# IRAMX-drv-v1.net
KiCad netlist of a schematic drawn in EAGLE
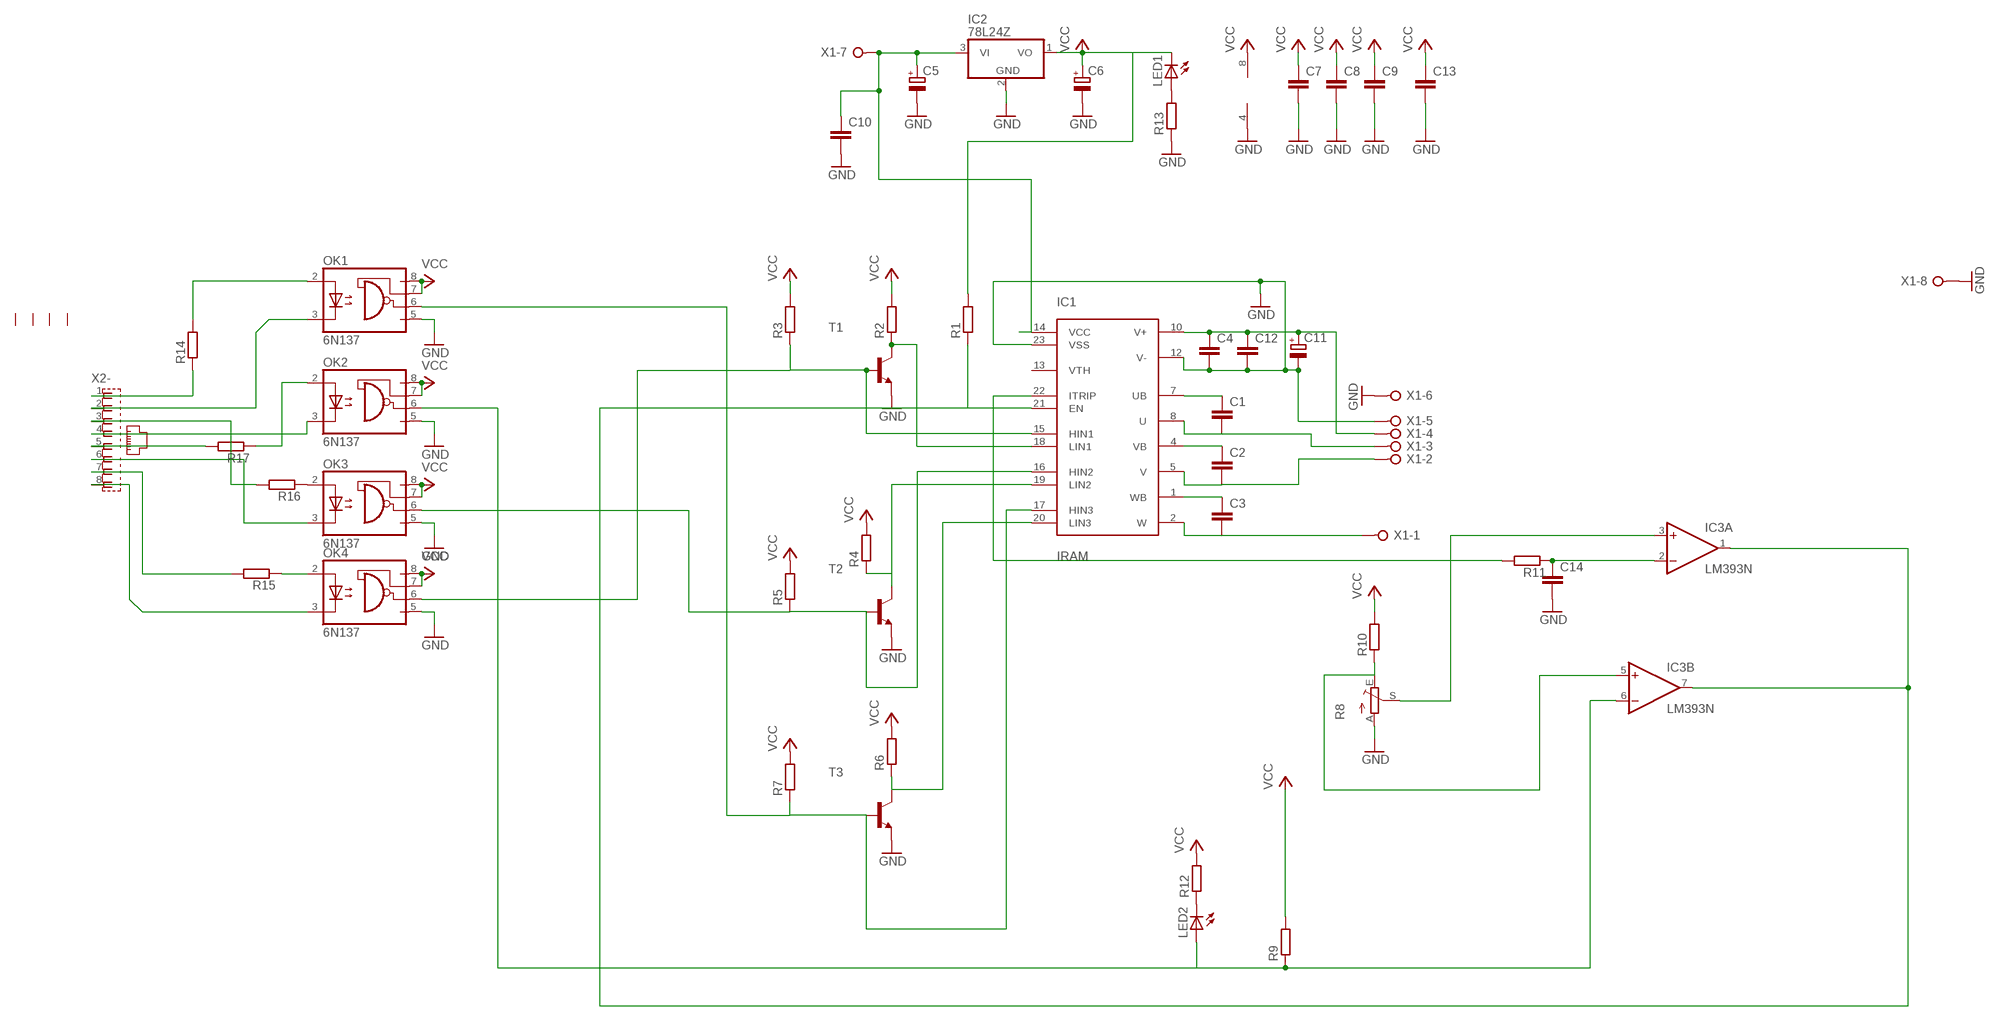
[diagram p0: schematic, sheet 1]

(export (version "E")
  (design (tool "Eeschema 10.0.6"))
  (components
    (comp (ref "C1")
      (value "C5/5")
      (footprint "eagle-import:C5B5")
      (libsource (lib "eagle-import") (part "C5/5"))
    )
    (comp (ref "C2")
      (value "C5/5")
      (footprint "eagle-import:C5B5")
      (libsource (lib "eagle-import") (part "C5/5"))
    )
    (comp (ref "C3")
      (value "C5/5")
      (footprint "eagle-import:C5B5")
      (libsource (lib "eagle-import") (part "C5/5"))
    )
    (comp (ref "C4")
      (value "C5/5")
      (footprint "eagle-import:C5B5")
      (libsource (lib "eagle-import") (part "C5/5"))
    )
    (comp (ref "C5")
      (value "CPOL-EUE2.5-5")
      (footprint "eagle-import:E2,5-5")
      (libsource (lib "eagle-import") (part "CPOL-EUE2.5-5"))
    )
    (comp (ref "C6")
      (value "CPOL-EUE2.5-5")
      (footprint "eagle-import:E2,5-5")
      (libsource (lib "eagle-import") (part "CPOL-EUE2.5-5"))
    )
    (comp (ref "C7")
      (value "C-EU050-025X075")
      (footprint "eagle-import:C050-025X075")
      (libsource (lib "eagle-import") (part "C-EU050-025X075"))
    )
    (comp (ref "C8")
      (value "C-EU050-025X075")
      (footprint "eagle-import:C050-025X075")
      (libsource (lib "eagle-import") (part "C-EU050-025X075"))
    )
    (comp (ref "C9")
      (value "C-EU050-025X075")
      (footprint "eagle-import:C050-025X075")
      (libsource (lib "eagle-import") (part "C-EU050-025X075"))
    )
    (comp (ref "C10")
      (value "C-EU050-025X075")
      (footprint "eagle-import:C050-025X075")
      (libsource (lib "eagle-import") (part "C-EU050-025X075"))
    )
    (comp (ref "C11")
      (value "CPOL-EUE10-25")
      (footprint "eagle-import:EB25D")
      (libsource (lib "eagle-import") (part "CPOL-EUE10-25"))
    )
    (comp (ref "C12")
      (value "C-EU150-054X183")
      (footprint "eagle-import:C150-054X183")
      (libsource (lib "eagle-import") (part "C-EU150-054X183"))
    )
    (comp (ref "C13")
      (value "C-EU050-025X075")
      (footprint "eagle-import:C050-025X075")
      (libsource (lib "eagle-import") (part "C-EU050-025X075"))
    )
    (comp (ref "C14")
      (value "C-EU050-025X075")
      (footprint "eagle-import:C050-025X075")
      (libsource (lib "eagle-import") (part "C-EU050-025X075"))
    )
    (comp (ref "IC1")
      (value "IRAM")
      (footprint "eagle-import:SIP23")
      (libsource (lib "eagle-import") (part "IRAM"))
    )
    (comp (ref "IC2")
      (value "78L24Z")
      (footprint "eagle-import:TO92")
      (libsource (lib "eagle-import") (part "78ZL24"))
    )
    (comp (ref "IC3")
      (value "LM393N")
      (footprint "eagle-import:DIL08")
      (libsource (lib "eagle-import") (part "LM393N"))
    )
    (comp (ref "LED1")
      (value "LED5MM")
      (footprint "eagle-import:LED5MM")
      (libsource (lib "eagle-import") (part "LED5MM"))
    )
    (comp (ref "LED2")
      (value "LED5MM")
      (footprint "eagle-import:LED5MM")
      (libsource (lib "eagle-import") (part "LED5MM"))
    )
    (comp (ref "OK1")
      (value "6N137")
      (footprint "eagle-import:DIL08")
      (libsource (lib "eagle-import") (part "6N137"))
    )
    (comp (ref "OK2")
      (value "6N137")
      (footprint "eagle-import:DIL08")
      (libsource (lib "eagle-import") (part "6N137"))
    )
    (comp (ref "OK3")
      (value "6N137")
      (footprint "eagle-import:DIL08")
      (libsource (lib "eagle-import") (part "6N137"))
    )
    (comp (ref "OK4")
      (value "6N137")
      (footprint "eagle-import:DIL08")
      (libsource (lib "eagle-import") (part "6N137"))
    )
    (comp (ref "R1")
      (value "R-EU_0204/7")
      (footprint "eagle-import:0204_7")
      (libsource (lib "eagle-import") (part "R-EU_0204/7"))
    )
    (comp (ref "R2")
      (value "R-EU_0204/7")
      (footprint "eagle-import:0204_7")
      (libsource (lib "eagle-import") (part "R-EU_0204/7"))
    )
    (comp (ref "R3")
      (value "R-EU_0204/7")
      (footprint "eagle-import:0204_7")
      (libsource (lib "eagle-import") (part "R-EU_0204/7"))
    )
    (comp (ref "R4")
      (value "R-EU_0204/7")
      (footprint "eagle-import:0204_7")
      (libsource (lib "eagle-import") (part "R-EU_0204/7"))
    )
    (comp (ref "R5")
      (value "R-EU_0204/7")
      (footprint "eagle-import:0204_7")
      (libsource (lib "eagle-import") (part "R-EU_0204/7"))
    )
    (comp (ref "R6")
      (value "R-EU_0204/7")
      (footprint "eagle-import:0204_7")
      (libsource (lib "eagle-import") (part "R-EU_0204/7"))
    )
    (comp (ref "R7")
      (value "R-EU_0204/7")
      (footprint "eagle-import:0204_7")
      (libsource (lib "eagle-import") (part "R-EU_0204/7"))
    )
    (comp (ref "R8")
      (value "TRIM_EU-CA6V")
      (footprint "eagle-import:CA6V")
      (libsource (lib "eagle-import") (part "TRIM_EU-CA6V"))
    )
    (comp (ref "R9")
      (value "R-EU_0204/7")
      (footprint "eagle-import:0204_7")
      (libsource (lib "eagle-import") (part "R-EU_0204/7"))
    )
    (comp (ref "R10")
      (value "R-EU_0204/7")
      (footprint "eagle-import:0204_7")
      (libsource (lib "eagle-import") (part "R-EU_0204/7"))
    )
    (comp (ref "R11")
      (value "R-EU_0204/7")
      (footprint "eagle-import:0204_7")
      (libsource (lib "eagle-import") (part "R-EU_0204/7"))
    )
    (comp (ref "R12")
      (value "R-EU_0204/7")
      (footprint "eagle-import:0204_7")
      (libsource (lib "eagle-import") (part "R-EU_0204/7"))
    )
    (comp (ref "R13")
      (value "R-EU_0204/7")
      (footprint "eagle-import:0204_7")
      (libsource (lib "eagle-import") (part "R-EU_0204/7"))
    )
    (comp (ref "R14")
      (value "R-EU_0204/2V")
      (footprint "eagle-import:0204V")
      (libsource (lib "eagle-import") (part "R-EU_0204/2V"))
    )
    (comp (ref "R15")
      (value "R-EU_0204/2V")
      (footprint "eagle-import:0204V")
      (libsource (lib "eagle-import") (part "R-EU_0204/2V"))
    )
    (comp (ref "R16")
      (value "R-EU_0204/2V")
      (footprint "eagle-import:0204V")
      (libsource (lib "eagle-import") (part "R-EU_0204/2V"))
    )
    (comp (ref "R17")
      (value "R-EU_0204/2V")
      (footprint "eagle-import:0204V")
      (libsource (lib "eagle-import") (part "R-EU_0204/2V"))
    )
    (comp (ref "T1")
      (value "BC547-NPN-TO92-CBE")
      (footprint "eagle-import:TO92-CBE")
      (libsource (lib "eagle-import") (part "-NPN-TO92-CBEBC547"))
    )
    (comp (ref "T2")
      (value "BC547-NPN-TO92-CBE")
      (footprint "eagle-import:TO92-CBE")
      (libsource (lib "eagle-import") (part "-NPN-TO92-CBEBC547"))
    )
    (comp (ref "T3")
      (value "BC547-NPN-TO92-CBE")
      (footprint "eagle-import:TO92-CBE")
      (libsource (lib "eagle-import") (part "-NPN-TO92-CBEBC547"))
    )
    (comp (ref "X1")
      (value "W237-08P")
      (footprint "eagle-import:W237-8P")
      (libsource (lib "eagle-import") (part "W237-08P"))
    )
    (comp (ref "X2")
      (value "RJ45")
      (footprint "eagle-import:RJ45")
      (libsource (lib "eagle-import") (part "RJ45"))
    )
  )
  (nets
    (net (code "1") (name "GND") (class "Default")
      (node (ref "C10") (pin "2") (pinfunction "2_2") (pintype "passive"))
      (node (ref "C11") (pin "-") (pinfunction "-_-") (pintype "passive"))
      (node (ref "C12") (pin "2") (pinfunction "2_2") (pintype "passive"))
      (node (ref "C13") (pin "2") (pinfunction "2_2") (pintype "passive"))
      (node (ref "C14") (pin "2") (pinfunction "2_2") (pintype "passive"))
      (node (ref "C4") (pin "2") (pinfunction "2_2") (pintype "passive"))
      (node (ref "C5") (pin "-") (pinfunction "-_-") (pintype "passive"))
      (node (ref "C6") (pin "-") (pinfunction "-_-") (pintype "passive"))
      (node (ref "C7") (pin "2") (pinfunction "2_2") (pintype "passive"))
      (node (ref "C8") (pin "2") (pinfunction "2_2") (pintype "passive"))
      (node (ref "C9") (pin "2") (pinfunction "2_2") (pintype "passive"))
      (node (ref "IC1") (pin "12") (pinfunction "V-_12") (pintype "bidirectional"))
      (node (ref "IC1") (pin "23") (pinfunction "VSS_23") (pintype "bidirectional"))
      (node (ref "IC2") (pin "2") (pinfunction "GND_2") (pintype "passive"))
      (node (ref "IC3") (pin "4") (pinfunction "V-_4") (pintype "power_in"))
      (node (ref "OK1") (pin "5") (pinfunction "GND_5") (pintype "passive"))
      (node (ref "OK2") (pin "5") (pinfunction "GND_5") (pintype "passive"))
      (node (ref "OK3") (pin "5") (pinfunction "GND_5") (pintype "passive"))
      (node (ref "OK4") (pin "5") (pinfunction "GND_5") (pintype "passive"))
      (node (ref "R13") (pin "1") (pinfunction "1_1") (pintype "passive"))
      (node (ref "R8") (pin "A") (pinfunction "A_A") (pintype "passive"))
      (node (ref "T1") (pin "E") (pinfunction "E_E") (pintype "passive"))
      (node (ref "T2") (pin "E") (pinfunction "E_E") (pintype "passive"))
      (node (ref "T3") (pin "E") (pinfunction "E_E") (pintype "passive"))
      (node (ref "X1") (pin "5") (pinfunction "KL_5") (pintype "passive"))
      (node (ref "X1") (pin "6") (pinfunction "KL_6") (pintype "passive"))
      (node (ref "X1") (pin "8") (pinfunction "KL_8") (pintype "passive"))
    )
    (net (code "2") (name "Net-(IC1-EN)") (class "Default")
      (node (ref "IC1") (pin "21") (pinfunction "EN_21") (pintype "bidirectional"))
      (node (ref "IC3") (pin "1") (pinfunction "OUT_1") (pintype "output"))
      (node (ref "IC3") (pin "7") (pinfunction "OUT_7") (pintype "output"))
      (node (ref "R1") (pin "1") (pinfunction "1_1") (pintype "passive"))
    )
    (net (code "3") (name "Net-(IC1-HIN1)") (class "Default")
      (node (ref "IC1") (pin "15") (pinfunction "HIN1_15") (pintype "bidirectional"))
      (node (ref "OK4") (pin "6") (pinfunction "VO_6") (pintype "passive"))
      (node (ref "R3") (pin "1") (pinfunction "1_1") (pintype "passive"))
      (node (ref "T1") (pin "B") (pinfunction "B_B") (pintype "passive"))
    )
    (net (code "4") (name "Net-(IC1-HIN2)") (class "Default")
      (node (ref "IC1") (pin "16") (pinfunction "HIN2_16") (pintype "bidirectional"))
      (node (ref "OK3") (pin "6") (pinfunction "VO_6") (pintype "passive"))
      (node (ref "R5") (pin "1") (pinfunction "1_1") (pintype "passive"))
      (node (ref "T2") (pin "B") (pinfunction "B_B") (pintype "passive"))
    )
    (net (code "5") (name "Net-(IC1-HIN3)") (class "Default")
      (node (ref "IC1") (pin "17") (pinfunction "HIN3_17") (pintype "bidirectional"))
      (node (ref "OK1") (pin "6") (pinfunction "VO_6") (pintype "passive"))
      (node (ref "R7") (pin "1") (pinfunction "1_1") (pintype "passive"))
      (node (ref "T3") (pin "B") (pinfunction "B_B") (pintype "passive"))
    )
    (net (code "6") (name "Net-(IC1-ITRIP)") (class "Default")
      (node (ref "IC1") (pin "22") (pinfunction "ITRIP_22") (pintype "bidirectional"))
      (node (ref "R11") (pin "2") (pinfunction "2_2") (pintype "passive"))
    )
    (net (code "7") (name "Net-(IC1-LIN1)") (class "Default")
      (node (ref "IC1") (pin "18") (pinfunction "LIN1_18") (pintype "bidirectional"))
      (node (ref "R2") (pin "1") (pinfunction "1_1") (pintype "passive"))
      (node (ref "T1") (pin "C") (pinfunction "C_C") (pintype "passive"))
    )
    (net (code "8") (name "Net-(IC1-LIN2)") (class "Default")
      (node (ref "IC1") (pin "19") (pinfunction "LIN2_19") (pintype "bidirectional"))
      (node (ref "R4") (pin "1") (pinfunction "1_1") (pintype "passive"))
      (node (ref "T2") (pin "C") (pinfunction "C_C") (pintype "passive"))
    )
    (net (code "9") (name "Net-(IC1-LIN3)") (class "Default")
      (node (ref "IC1") (pin "20") (pinfunction "LIN3_20") (pintype "bidirectional"))
      (node (ref "R6") (pin "1") (pinfunction "1_1") (pintype "passive"))
      (node (ref "T3") (pin "C") (pinfunction "C_C") (pintype "passive"))
    )
    (net (code "10") (name "Net-(IC1-U)") (class "Default")
      (node (ref "C1") (pin "2") (pinfunction "2_2") (pintype "passive"))
      (node (ref "IC1") (pin "8") (pinfunction "U_8") (pintype "bidirectional"))
      (node (ref "X1") (pin "3") (pinfunction "KL_3") (pintype "passive"))
    )
    (net (code "11") (name "Net-(IC1-UB)") (class "Default")
      (node (ref "C1") (pin "1") (pinfunction "1_1") (pintype "passive"))
      (node (ref "IC1") (pin "7") (pinfunction "UB_7") (pintype "bidirectional"))
    )
    (net (code "12") (name "Net-(IC1-V)") (class "Default")
      (node (ref "C2") (pin "2") (pinfunction "2_2") (pintype "passive"))
      (node (ref "IC1") (pin "5") (pinfunction "V_5") (pintype "bidirectional"))
      (node (ref "X1") (pin "2") (pinfunction "KL_2") (pintype "passive"))
    )
    (net (code "13") (name "Net-(IC1-V+)") (class "Default")
      (node (ref "C11") (pin "+") (pinfunction "+_+") (pintype "passive"))
      (node (ref "C12") (pin "1") (pinfunction "1_1") (pintype "passive"))
      (node (ref "C4") (pin "1") (pinfunction "1_1") (pintype "passive"))
      (node (ref "IC1") (pin "10") (pinfunction "V+_10") (pintype "bidirectional"))
      (node (ref "X1") (pin "4") (pinfunction "KL_4") (pintype "passive"))
    )
    (net (code "14") (name "Net-(IC1-VB)") (class "Default")
      (node (ref "C2") (pin "1") (pinfunction "1_1") (pintype "passive"))
      (node (ref "IC1") (pin "4") (pinfunction "VB_4") (pintype "bidirectional"))
    )
    (net (code "15") (name "Net-(IC1-VCC)") (class "Default")
      (node (ref "C10") (pin "1") (pinfunction "1_1") (pintype "passive"))
      (node (ref "C5") (pin "+") (pinfunction "+_+") (pintype "passive"))
      (node (ref "IC1") (pin "14") (pinfunction "VCC_14") (pintype "bidirectional"))
      (node (ref "IC2") (pin "3") (pinfunction "VI_3") (pintype "input"))
      (node (ref "X1") (pin "7") (pinfunction "KL_7") (pintype "passive"))
    )
    (net (code "16") (name "Net-(IC1-W)") (class "Default")
      (node (ref "C3") (pin "2") (pinfunction "2_2") (pintype "passive"))
      (node (ref "IC1") (pin "2") (pinfunction "W_2") (pintype "bidirectional"))
      (node (ref "X1") (pin "1") (pinfunction "KL_1") (pintype "passive"))
    )
    (net (code "17") (name "Net-(IC1-WB)") (class "Default")
      (node (ref "C3") (pin "1") (pinfunction "1_1") (pintype "passive"))
      (node (ref "IC1") (pin "1") (pinfunction "WB_1") (pintype "bidirectional"))
    )
    (net (code "18") (name "Net-(IC3A-+IN)") (class "Default")
      (node (ref "IC3") (pin "3") (pinfunction "+IN_3") (pintype "input"))
      (node (ref "R8") (pin "S") (pinfunction "S_S") (pintype "passive"))
    )
    (net (code "19") (name "Net-(IC3A--IN)") (class "Default")
      (node (ref "C14") (pin "1") (pinfunction "1_1") (pintype "passive"))
      (node (ref "IC3") (pin "2") (pinfunction "-IN_2") (pintype "input"))
      (node (ref "R11") (pin "1") (pinfunction "1_1") (pintype "passive"))
    )
    (net (code "20") (name "Net-(IC3B-+IN)") (class "Default")
      (node (ref "IC3") (pin "5") (pinfunction "+IN_5") (pintype "input"))
      (node (ref "R10") (pin "1") (pinfunction "1_1") (pintype "passive"))
      (node (ref "R8") (pin "E") (pinfunction "E_E") (pintype "passive"))
    )
    (net (code "21") (name "Net-(IC3B--IN)") (class "Default")
      (node (ref "IC3") (pin "6") (pinfunction "-IN_6") (pintype "input"))
      (node (ref "LED2") (pin "A") (pinfunction "A_A") (pintype "passive"))
      (node (ref "OK2") (pin "6") (pinfunction "VO_6") (pintype "passive"))
      (node (ref "R9") (pin "1") (pinfunction "1_1") (pintype "passive"))
    )
    (net (code "22") (name "Net-(LED1-PadA)") (class "Default")
      (node (ref "LED1") (pin "A") (pinfunction "A_A") (pintype "passive"))
      (node (ref "R13") (pin "2") (pinfunction "2_2") (pintype "passive"))
    )
    (net (code "23") (name "Net-(LED2-C)") (class "Default")
      (node (ref "LED2") (pin "K") (pinfunction "C_K") (pintype "passive"))
      (node (ref "R12") (pin "1") (pinfunction "1_1") (pintype "passive"))
    )
    (net (code "24") (name "Net-(OK1-A)") (class "Default")
      (node (ref "OK1") (pin "2") (pinfunction "A_2") (pintype "passive"))
      (node (ref "R14") (pin "2") (pinfunction "2_2") (pintype "passive"))
    )
    (net (code "25") (name "Net-(OK1-C)") (class "Default")
      (node (ref "OK1") (pin "3") (pinfunction "C_3") (pintype "passive"))
      (node (ref "X2") (pin "2") (pinfunction "2_2") (pintype "passive"))
    )
    (net (code "26") (name "Net-(OK2-A)") (class "Default")
      (node (ref "OK2") (pin "2") (pinfunction "A_2") (pintype "passive"))
      (node (ref "R17") (pin "1") (pinfunction "1_1") (pintype "passive"))
    )
    (net (code "27") (name "Net-(OK2-C)") (class "Default")
      (node (ref "OK2") (pin "3") (pinfunction "C_3") (pintype "passive"))
      (node (ref "X2") (pin "4") (pinfunction "4_4") (pintype "passive"))
    )
    (net (code "28") (name "Net-(OK3-A)") (class "Default")
      (node (ref "OK3") (pin "2") (pinfunction "A_2") (pintype "passive"))
      (node (ref "R16") (pin "1") (pinfunction "1_1") (pintype "passive"))
    )
    (net (code "29") (name "Net-(OK3-C)") (class "Default")
      (node (ref "OK3") (pin "3") (pinfunction "C_3") (pintype "passive"))
      (node (ref "X2") (pin "6") (pinfunction "6_6") (pintype "passive"))
    )
    (net (code "30") (name "Net-(OK4-A)") (class "Default")
      (node (ref "OK4") (pin "2") (pinfunction "A_2") (pintype "passive"))
      (node (ref "R15") (pin "1") (pinfunction "1_1") (pintype "passive"))
    )
    (net (code "31") (name "Net-(OK4-C)") (class "Default")
      (node (ref "OK4") (pin "3") (pinfunction "C_3") (pintype "passive"))
      (node (ref "X2") (pin "8") (pinfunction "8_8") (pintype "passive"))
    )
    (net (code "32") (name "Net-(R14-Pad1)") (class "Default")
      (node (ref "R14") (pin "1") (pinfunction "1_1") (pintype "passive"))
      (node (ref "X2") (pin "1") (pinfunction "1_1") (pintype "passive"))
    )
    (net (code "33") (name "Net-(R15-Pad2)") (class "Default")
      (node (ref "R15") (pin "2") (pinfunction "2_2") (pintype "passive"))
      (node (ref "X2") (pin "7") (pinfunction "7_7") (pintype "passive"))
    )
    (net (code "34") (name "Net-(R16-Pad2)") (class "Default")
      (node (ref "R16") (pin "2") (pinfunction "2_2") (pintype "passive"))
      (node (ref "X2") (pin "3") (pinfunction "3_3") (pintype "passive"))
    )
    (net (code "35") (name "Net-(R17-Pad2)") (class "Default")
      (node (ref "R17") (pin "2") (pinfunction "2_2") (pintype "passive"))
      (node (ref "X2") (pin "5") (pinfunction "5_5") (pintype "passive"))
    )
    (net (code "36") (name "VCC") (class "Default")
      (node (ref "C13") (pin "1") (pinfunction "1_1") (pintype "passive"))
      (node (ref "C6") (pin "+") (pinfunction "+_+") (pintype "passive"))
      (node (ref "C7") (pin "1") (pinfunction "1_1") (pintype "passive"))
      (node (ref "C8") (pin "1") (pinfunction "1_1") (pintype "passive"))
      (node (ref "C9") (pin "1") (pinfunction "1_1") (pintype "passive"))
      (node (ref "IC2") (pin "1") (pinfunction "VO_1") (pintype "passive"))
      (node (ref "IC3") (pin "8") (pinfunction "V+_8") (pintype "power_in"))
      (node (ref "LED1") (pin "K") (pinfunction "C_K") (pintype "passive"))
      (node (ref "OK1") (pin "7") (pinfunction "VE_7") (pintype "passive"))
      (node (ref "OK1") (pin "8") (pinfunction "VCC_8") (pintype "passive"))
      (node (ref "OK2") (pin "7") (pinfunction "VE_7") (pintype "passive"))
      (node (ref "OK2") (pin "8") (pinfunction "VCC_8") (pintype "passive"))
      (node (ref "OK3") (pin "7") (pinfunction "VE_7") (pintype "passive"))
      (node (ref "OK3") (pin "8") (pinfunction "VCC_8") (pintype "passive"))
      (node (ref "OK4") (pin "7") (pinfunction "VE_7") (pintype "passive"))
      (node (ref "OK4") (pin "8") (pinfunction "VCC_8") (pintype "passive"))
      (node (ref "R1") (pin "2") (pinfunction "2_2") (pintype "passive"))
      (node (ref "R10") (pin "2") (pinfunction "2_2") (pintype "passive"))
      (node (ref "R12") (pin "2") (pinfunction "2_2") (pintype "passive"))
      (node (ref "R2") (pin "2") (pinfunction "2_2") (pintype "passive"))
      (node (ref "R3") (pin "2") (pinfunction "2_2") (pintype "passive"))
      (node (ref "R4") (pin "2") (pinfunction "2_2") (pintype "passive"))
      (node (ref "R5") (pin "2") (pinfunction "2_2") (pintype "passive"))
      (node (ref "R6") (pin "2") (pinfunction "2_2") (pintype "passive"))
      (node (ref "R7") (pin "2") (pinfunction "2_2") (pintype "passive"))
      (node (ref "R9") (pin "2") (pinfunction "2_2") (pintype "passive"))
    )
    (net (code "37") (name "unconnected-(IC1-VTH-Pad13)") (class "Default")
      (node (ref "IC1") (pin "13") (pinfunction "VTH_13") (pintype "bidirectional"))
    )
    (net (code "38") (name "unconnected-(X2B-1-PadG1)") (class "Default")
      (node (ref "X2") (pin "G1") (pinfunction "1_G1") (pintype "passive"))
    )
    (net (code "39") (name "unconnected-(X2C-1-PadG2)") (class "Default")
      (node (ref "X2") (pin "G2") (pinfunction "1_G2") (pintype "passive"))
    )
    (net (code "40") (name "unconnected-(X2D-1-PadG3)") (class "Default")
      (node (ref "X2") (pin "G3") (pinfunction "1_G3") (pintype "passive"))
    )
    (net (code "41") (name "unconnected-(X2E-1-PadG4)") (class "Default")
      (node (ref "X2") (pin "G4") (pinfunction "1_G4") (pintype "passive"))
    )
  )
)
